# ESP-32-VEZERLO-V1.net
KiCad netlist of a schematic drawn in EAGLE
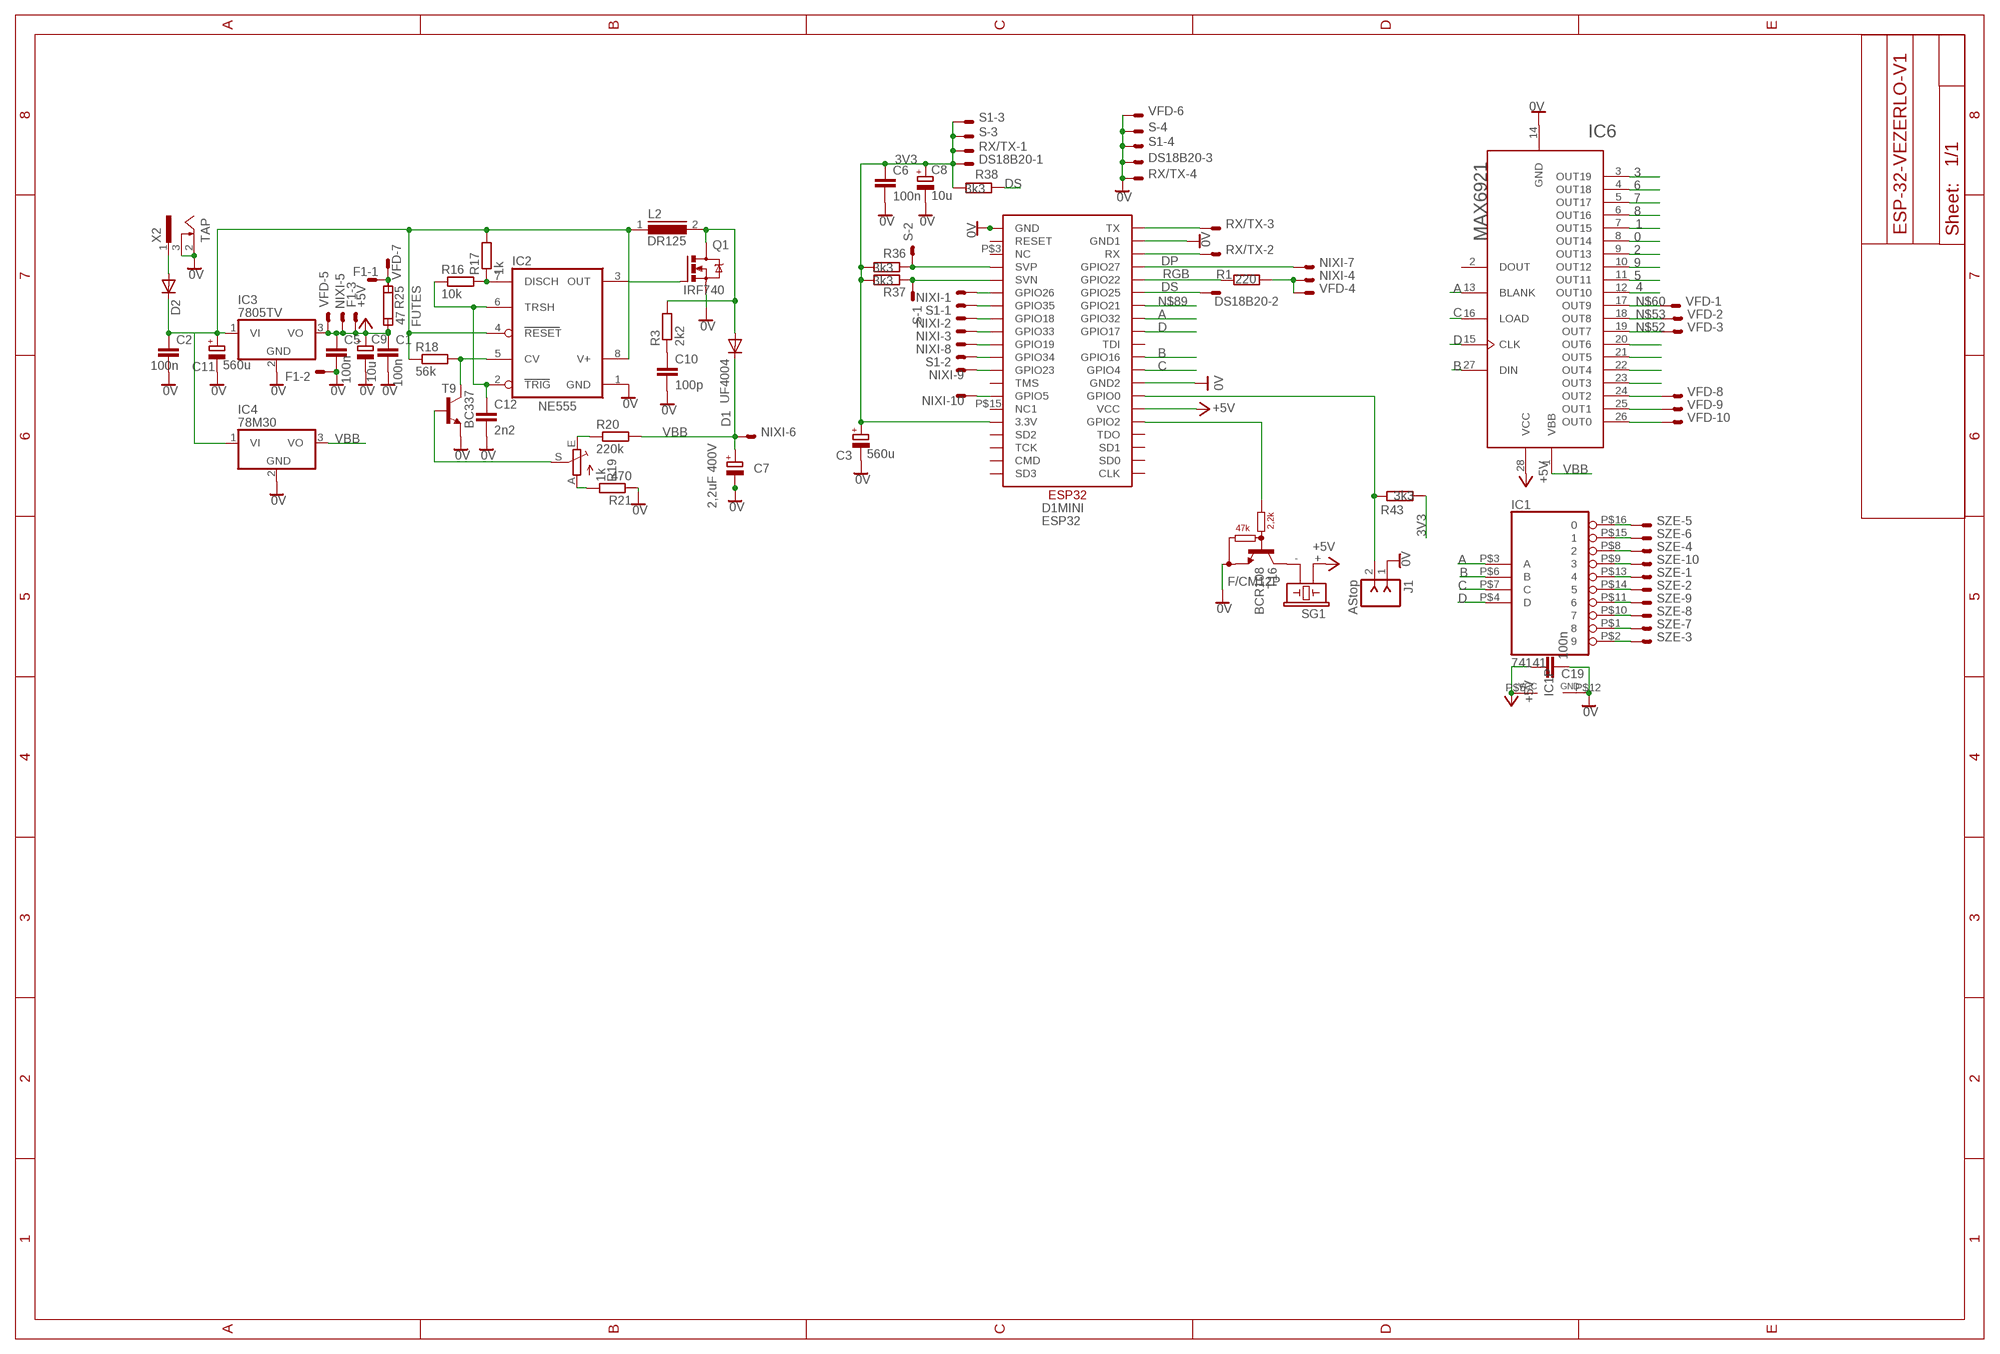
[diagram p0: schematic, sheet 1]

(export (version "E")
  (design (tool "Eeschema 10.0.6"))
  (components
    (comp (ref "C1")
      (value "100n")
      (footprint "eagle-import:0603")
      (libsource (lib "eagle-import") (part "C0603"))
    )
    (comp (ref "C2")
      (value "100n")
      (footprint "eagle-import:0603")
      (libsource (lib "eagle-import") (part "C0603"))
    )
    (comp (ref "C3")
      (value "560u")
      (footprint "eagle-import:E5-8,5")
      (libsource (lib "eagle-import") (part "CPOL-EUE5-8.5"))
    )
    (comp (ref "C5")
      (value "100n")
      (footprint "eagle-import:0603")
      (libsource (lib "eagle-import") (part "C0603"))
    )
    (comp (ref "C6")
      (value "100n")
      (footprint "eagle-import:0603")
      (libsource (lib "eagle-import") (part "C0603"))
    )
    (comp (ref "C7")
      (value "2,2uF 400V")
      (footprint "eagle-import:E2,5-7")
      (libsource (lib "eagle-import") (part "CPOL-EUE2.5-7"))
    )
    (comp (ref "C8")
      (value "10u")
      (footprint "eagle-import:E2,5-5")
      (libsource (lib "eagle-import") (part "CPOL-EUE2.5-5"))
    )
    (comp (ref "C9")
      (value "10u")
      (footprint "eagle-import:E2,5-5")
      (libsource (lib "eagle-import") (part "CPOL-EUE2.5-5"))
    )
    (comp (ref "C10")
      (value "100p")
      (footprint "eagle-import:C050-024X044")
      (libsource (lib "eagle-import") (part "C-EU050-024X044"))
    )
    (comp (ref "C11")
      (value "560u")
      (footprint "eagle-import:E5-8,5")
      (libsource (lib "eagle-import") (part "CPOL-EUE5-8.5"))
    )
    (comp (ref "C12")
      (value "2n2")
      (footprint "eagle-import:C0603")
      (libsource (lib "eagle-import") (part "C-EUC0603"))
    )
    (comp (ref "C19")
      (value "100n")
      (footprint "eagle-import:0603")
      (libsource (lib "eagle-import") (part "C0603"))
    )
    (comp (ref "D1")
      (value "UF4004")
      (footprint "eagle-import:DO35-10")
      (libsource (lib "eagle-import") (part "BA221"))
    )
    (comp (ref "D1MINI")
      (value "ESP32")
      (footprint "eagle-import:ESP32-2X20")
      (libsource (lib "eagle-import") (part "ESP32-2X20"))
    )
    (comp (ref "D2")
      (value "DIODE-SOD123")
      (footprint "eagle-import:SOD123")
      (libsource (lib "eagle-import") (part "DIODE-SOD123"))
    )
    (comp (ref "DS18B20")
      (value "PAD3")
      (footprint "eagle-import:PAD3")
      (libsource (lib "eagle-import") (part "PAD3"))
    )
    (comp (ref "F1")
      (value "PAD3")
      (footprint "eagle-import:PAD3")
      (libsource (lib "eagle-import") (part "PAD3"))
    )
    (comp (ref "FUTES")
      (value "47")
      (footprint "eagle-import:0207_10")
      (libsource (lib "eagle-import") (part "R-EU_0207/10"))
    )
    (comp (ref "IC1")
      (value "74141")
      (footprint "eagle-import:DIL16SMD")
      (libsource (lib "eagle-import") (part "74141"))
    )
    (comp (ref "IC2")
      (value "NE555")
      (footprint "eagle-import:DIL08")
      (fields (field (name "MF") "MAXIM") (field (name "MPN") "ICM7555IPA+"))
      (libsource (lib "eagle-import") (part "ICM7555"))
    )
    (comp (ref "IC3")
      (value "7805TV")
      (footprint "eagle-import:TO220V")
      (libsource (lib "eagle-import") (part "78TV05"))
    )
    (comp (ref "IC4")
      (value "78M30")
      (footprint "eagle-import:TO220V")
      (libsource (lib "eagle-import") (part "78TV05"))
    )
    (comp (ref "IC6")
      (value "MAX6921")
      (footprint "eagle-import:SO-28W")
      (libsource (lib "eagle-import") (part "MAX6921SOIC28W"))
    )
    (comp (ref "J1")
      (value "AStop")
      (footprint "eagle-import:SIP-100-02-32")
      (libsource (lib "eagle-import") (part "F-1X02-SIP-100-32"))
    )
    (comp (ref "L2")
      (value "DR125")
      (footprint "eagle-import:DR125")
      (libsource (lib "eagle-import") (part "DR125"))
    )
    (comp (ref "NIXI")
      (value "PAD10")
      (footprint "eagle-import:PAD10")
      (libsource (lib "eagle-import") (part "PAD10"))
    )
    (comp (ref "Q1")
      (value "IRF740")
      (footprint "eagle-import:TO220BV")
      (libsource (lib "eagle-import") (part "IRF740"))
    )
    (comp (ref "R1")
      (value "220")
      (footprint "eagle-import:0603")
      (libsource (lib "eagle-import") (part "R0603"))
    )
    (comp (ref "R3")
      (value "2k2")
      (footprint "eagle-import:0204_7")
      (libsource (lib "eagle-import") (part "R-EU_0204/7"))
    )
    (comp (ref "R16")
      (value "10k")
      (footprint "eagle-import:R0603")
      (libsource (lib "eagle-import") (part "R-EU_R0603"))
    )
    (comp (ref "R17")
      (value "1k")
      (footprint "eagle-import:R0603")
      (libsource (lib "eagle-import") (part "R-EU_R0603"))
    )
    (comp (ref "R18")
      (value "56k")
      (footprint "eagle-import:R0603")
      (libsource (lib "eagle-import") (part "R-EU_R0603"))
    )
    (comp (ref "R19")
      (value "1k")
      (footprint "eagle-import:CA6H")
      (libsource (lib "eagle-import") (part "TRIM_EU-CA6H"))
    )
    (comp (ref "R20")
      (value "220k")
      (footprint "eagle-import:0204_7")
      (libsource (lib "eagle-import") (part "R-EU_0204/7"))
    )
    (comp (ref "R21")
      (value "470")
      (footprint "eagle-import:0204_7")
      (libsource (lib "eagle-import") (part "R-EU_0204/7"))
    )
    (comp (ref "R25")
      (value "RCA0001")
      (footprint "eagle-import:CA0001")
      (libsource (lib "eagle-import") (part "RCA0001"))
    )
    (comp (ref "R36")
      (value "3k3")
      (footprint "eagle-import:0603")
      (libsource (lib "eagle-import") (part "R0603"))
    )
    (comp (ref "R37")
      (value "3k3")
      (footprint "eagle-import:0603")
      (libsource (lib "eagle-import") (part "R0603"))
    )
    (comp (ref "R38")
      (value "3k3")
      (footprint "eagle-import:0603")
      (libsource (lib "eagle-import") (part "R0603"))
    )
    (comp (ref "R43")
      (value "3k3")
      (footprint "eagle-import:0603")
      (libsource (lib "eagle-import") (part "R0603"))
    )
    (comp (ref "RX/TX")
      (value "PAD4")
      (footprint "eagle-import:PAD4")
      (libsource (lib "eagle-import") (part "PAD4"))
    )
    (comp (ref "S")
      (value "PAD4")
      (footprint "eagle-import:PAD4")
      (libsource (lib "eagle-import") (part "PAD4"))
    )
    (comp (ref "S1")
      (value "PAD4")
      (footprint "eagle-import:PAD4")
      (libsource (lib "eagle-import") (part "PAD4"))
    )
    (comp (ref "SG1")
      (value "F/CM12P")
      (footprint "eagle-import:F_CM12P")
      (libsource (lib "eagle-import") (part "F/CM12P"))
    )
    (comp (ref "SZE")
      (value "PAD10")
      (footprint "eagle-import:PAD10")
      (libsource (lib "eagle-import") (part "PAD10"))
    )
    (comp (ref "T9")
      (value "BC337")
      (footprint "eagle-import:SOT23-BEC")
      (libsource (lib "eagle-import") (part "-NPN-SOT23-BECBC847"))
    )
    (comp (ref "T16")
      (value "BCR108")
      (footprint "eagle-import:SOT23-BEC")
      (libsource (lib "eagle-import") (part "BCR108"))
    )
    (comp (ref "VFD")
      (value "PAD10")
      (footprint "eagle-import:PAD10")
      (libsource (lib "eagle-import") (part "PAD10"))
    )
    (comp (ref "X2")
      (value "TAP")
      (footprint "eagle-import:TAP")
      (libsource (lib "eagle-import") (part "TAP"))
    )
  )
  (nets
    (net (code "1") (name "+5V") (class "Default")
      (node (ref "C1") (pin "1") (pinfunction "1_1") (pintype "passive"))
      (node (ref "C19") (pin "1") (pinfunction "1_1") (pintype "passive"))
      (node (ref "C5") (pin "1") (pinfunction "1_1") (pintype "passive"))
      (node (ref "C9") (pin "+") (pinfunction "+_+") (pintype "passive"))
      (node (ref "D1MINI") (pin "P$35") (pinfunction "VCC_P$35") (pintype "bidirectional"))
      (node (ref "F1") (pin "P$3") (pinfunction "S_P$3") (pintype "passive"))
      (node (ref "FUTES") (pin "1") (pinfunction "1_1") (pintype "passive"))
      (node (ref "IC1") (pin "P$5") (pinfunction "VCC_P$5") (pintype "power_in"))
      (node (ref "IC3") (pin "3") (pinfunction "VO_3") (pintype "passive"))
      (node (ref "IC6") (pin "28") (pinfunction "VCC_28") (pintype "power_in"))
      (node (ref "NIXI") (pin "P$5") (pinfunction "S_P$5") (pintype "passive"))
      (node (ref "R25") (pin "1") (pinfunction "1_1") (pintype "passive"))
      (node (ref "SG1") (pin "+") (pinfunction "1_+") (pintype "passive"))
      (node (ref "VFD") (pin "P$5") (pinfunction "S_P$5") (pintype "passive"))
    )
    (net (code "2") (name "/0") (class "Default")
      (node (ref "IC1") (pin "P$16") (pinfunction "0_P$16") (pintype "open_collector"))
      (node (ref "IC6") (pin "8") (pinfunction "OUT14_8") (pintype "output"))
      (node (ref "SZE") (pin "P$5") (pinfunction "S_P$5") (pintype "passive"))
    )
    (net (code "3") (name "/1") (class "Default")
      (node (ref "IC1") (pin "P$15") (pinfunction "1_P$15") (pintype "open_collector"))
      (node (ref "IC6") (pin "7") (pinfunction "OUT15_7") (pintype "output"))
      (node (ref "SZE") (pin "P$6") (pinfunction "S_P$6") (pintype "passive"))
    )
    (net (code "4") (name "/2") (class "Default")
      (node (ref "IC1") (pin "P$8") (pinfunction "2_P$8") (pintype "open_collector"))
      (node (ref "IC6") (pin "9") (pinfunction "OUT13_9") (pintype "output"))
      (node (ref "SZE") (pin "P$4") (pinfunction "S_P$4") (pintype "passive"))
    )
    (net (code "5") (name "/3") (class "Default")
      (node (ref "IC1") (pin "P$9") (pinfunction "3_P$9") (pintype "open_collector"))
      (node (ref "IC6") (pin "3") (pinfunction "OUT19_3") (pintype "output"))
      (node (ref "SZE") (pin "P$10") (pinfunction "S_P$10") (pintype "passive"))
    )
    (net (code "6") (name "/3V3") (class "Default")
      (node (ref "C3") (pin "+") (pinfunction "+_+") (pintype "passive"))
      (node (ref "C6") (pin "1") (pinfunction "1_1") (pintype "passive"))
      (node (ref "C8") (pin "+") (pinfunction "+_+") (pintype "passive"))
      (node (ref "D1MINI") (pin "P$16") (pinfunction "3.3V_P$16") (pintype "bidirectional"))
      (node (ref "DS18B20") (pin "P$1") (pinfunction "S_P$1") (pintype "passive"))
      (node (ref "R36") (pin "2") (pinfunction "2_2") (pintype "passive"))
      (node (ref "R37") (pin "2") (pinfunction "2_2") (pintype "passive"))
      (node (ref "R38") (pin "2") (pinfunction "2_2") (pintype "passive"))
      (node (ref "R43") (pin "2") (pinfunction "2_2") (pintype "passive"))
      (node (ref "RX/TX") (pin "P$1") (pinfunction "S_P$1") (pintype "passive"))
      (node (ref "S") (pin "P$3") (pinfunction "S_P$3") (pintype "passive"))
      (node (ref "S1") (pin "P$3") (pinfunction "S_P$3") (pintype "passive"))
    )
    (net (code "7") (name "/4") (class "Default")
      (node (ref "IC1") (pin "P$13") (pinfunction "4_P$13") (pintype "open_collector"))
      (node (ref "IC6") (pin "12") (pinfunction "OUT10_12") (pintype "output"))
      (node (ref "SZE") (pin "P$1") (pinfunction "S_P$1") (pintype "passive"))
    )
    (net (code "8") (name "/5") (class "Default")
      (node (ref "IC1") (pin "P$14") (pinfunction "5_P$14") (pintype "open_collector"))
      (node (ref "IC6") (pin "11") (pinfunction "OUT11_11") (pintype "output"))
      (node (ref "SZE") (pin "P$2") (pinfunction "S_P$2") (pintype "passive"))
    )
    (net (code "9") (name "/6") (class "Default")
      (node (ref "IC1") (pin "P$11") (pinfunction "6_P$11") (pintype "open_collector"))
      (node (ref "IC6") (pin "4") (pinfunction "OUT18_4") (pintype "output"))
      (node (ref "SZE") (pin "P$9") (pinfunction "S_P$9") (pintype "passive"))
    )
    (net (code "10") (name "/7") (class "Default")
      (node (ref "IC1") (pin "P$10") (pinfunction "7_P$10") (pintype "open_collector"))
      (node (ref "IC6") (pin "5") (pinfunction "OUT17_5") (pintype "output"))
      (node (ref "SZE") (pin "P$8") (pinfunction "S_P$8") (pintype "passive"))
    )
    (net (code "11") (name "/8") (class "Default")
      (node (ref "IC1") (pin "P$1") (pinfunction "8_P$1") (pintype "open_collector"))
      (node (ref "IC6") (pin "6") (pinfunction "OUT16_6") (pintype "output"))
      (node (ref "SZE") (pin "P$7") (pinfunction "S_P$7") (pintype "passive"))
    )
    (net (code "12") (name "/9") (class "Default")
      (node (ref "IC1") (pin "P$2") (pinfunction "9_P$2") (pintype "open_collector"))
      (node (ref "IC6") (pin "10") (pinfunction "OUT12_10") (pintype "output"))
      (node (ref "SZE") (pin "P$3") (pinfunction "S_P$3") (pintype "passive"))
    )
    (net (code "13") (name "/A") (class "Default")
      (node (ref "D1MINI") (pin "P$28") (pinfunction "GPIO32_P$28") (pintype "bidirectional"))
      (node (ref "IC1") (pin "P$3") (pinfunction "A_P$3") (pintype "input"))
      (node (ref "IC6") (pin "13") (pinfunction "BLANK_13") (pintype "input"))
    )
    (net (code "14") (name "/B") (class "Default")
      (node (ref "D1MINI") (pin "P$31") (pinfunction "GPIO16_P$31") (pintype "bidirectional"))
      (node (ref "IC1") (pin "P$6") (pinfunction "B_P$6") (pintype "input"))
      (node (ref "IC6") (pin "27") (pinfunction "DIN_27") (pintype "input"))
    )
    (net (code "15") (name "/C") (class "Default")
      (node (ref "D1MINI") (pin "P$32") (pinfunction "GPIO4_P$32") (pintype "bidirectional"))
      (node (ref "IC1") (pin "P$7") (pinfunction "C_P$7") (pintype "input"))
      (node (ref "IC6") (pin "16") (pinfunction "LOAD_16") (pintype "input"))
    )
    (net (code "16") (name "/D") (class "Default")
      (node (ref "D1MINI") (pin "P$29") (pinfunction "GPIO17_P$29") (pintype "bidirectional"))
      (node (ref "IC1") (pin "P$4") (pinfunction "D_P$4") (pintype "input"))
      (node (ref "IC6") (pin "15") (pinfunction "CLK_15") (pintype "input"))
    )
    (net (code "17") (name "/DP") (class "Default")
      (node (ref "D1MINI") (pin "P$24") (pinfunction "GPIO27_P$24") (pintype "bidirectional"))
      (node (ref "NIXI") (pin "P$7") (pinfunction "S_P$7") (pintype "passive"))
    )
    (net (code "18") (name "/DS") (class "Default")
      (node (ref "D1MINI") (pin "P$26") (pinfunction "GPIO25_P$26") (pintype "bidirectional"))
      (node (ref "DS18B20") (pin "P$2") (pinfunction "S_P$2") (pintype "passive"))
      (node (ref "R38") (pin "1") (pinfunction "1_1") (pintype "passive"))
    )
    (net (code "19") (name "/N$52") (class "Default")
      (node (ref "IC6") (pin "19") (pinfunction "OUT7_19") (pintype "output"))
      (node (ref "VFD") (pin "P$3") (pinfunction "S_P$3") (pintype "passive"))
    )
    (net (code "20") (name "/N$53") (class "Default")
      (node (ref "IC6") (pin "18") (pinfunction "OUT8_18") (pintype "output"))
      (node (ref "VFD") (pin "P$2") (pinfunction "S_P$2") (pintype "passive"))
    )
    (net (code "21") (name "/N$60") (class "Default")
      (node (ref "IC6") (pin "17") (pinfunction "OUT9_17") (pintype "output"))
      (node (ref "VFD") (pin "P$1") (pinfunction "S_P$1") (pintype "passive"))
    )
    (net (code "22") (name "/N$89") (class "Default")
      (node (ref "D1MINI") (pin "P$27") (pinfunction "GPIO21_P$27") (pintype "bidirectional"))
    )
    (net (code "23") (name "/RGB") (class "Default")
      (node (ref "D1MINI") (pin "P$25") (pinfunction "GPIO22_P$25") (pintype "bidirectional"))
      (node (ref "R1") (pin "2") (pinfunction "2_2") (pintype "passive"))
    )
    (net (code "24") (name "/VBB") (class "Default")
      (node (ref "C7") (pin "+") (pinfunction "+_+") (pintype "passive"))
      (node (ref "D1") (pin "C") (pinfunction "C_C") (pintype "passive"))
      (node (ref "IC4") (pin "3") (pinfunction "VO_3") (pintype "passive"))
      (node (ref "IC6") (pin "1") (pinfunction "VBB_1") (pintype "power_in"))
      (node (ref "NIXI") (pin "P$6") (pinfunction "S_P$6") (pintype "passive"))
      (node (ref "R20") (pin "2") (pinfunction "2_2") (pintype "passive"))
    )
    (net (code "25") (name "0V") (class "Default")
      (node (ref "C1") (pin "2") (pinfunction "2_2") (pintype "passive"))
      (node (ref "C10") (pin "2") (pinfunction "2_2") (pintype "passive"))
      (node (ref "C11") (pin "-") (pinfunction "-_-") (pintype "passive"))
      (node (ref "C12") (pin "2") (pinfunction "2_2") (pintype "passive"))
      (node (ref "C19") (pin "2") (pinfunction "2_2") (pintype "passive"))
      (node (ref "C2") (pin "2") (pinfunction "2_2") (pintype "passive"))
      (node (ref "C3") (pin "-") (pinfunction "-_-") (pintype "passive"))
      (node (ref "C5") (pin "2") (pinfunction "2_2") (pintype "passive"))
      (node (ref "C6") (pin "2") (pinfunction "2_2") (pintype "passive"))
      (node (ref "C7") (pin "-") (pinfunction "-_-") (pintype "passive"))
      (node (ref "C8") (pin "-") (pinfunction "-_-") (pintype "passive"))
      (node (ref "C9") (pin "-") (pinfunction "-_-") (pintype "passive"))
      (node (ref "D1MINI") (pin "P$1") (pinfunction "GND_P$1") (pintype "bidirectional"))
      (node (ref "D1MINI") (pin "P$22") (pinfunction "GND1_P$22") (pintype "bidirectional"))
      (node (ref "D1MINI") (pin "P$33") (pinfunction "GND2_P$33") (pintype "bidirectional"))
      (node (ref "DS18B20") (pin "P$3") (pinfunction "S_P$3") (pintype "passive"))
      (node (ref "F1") (pin "P$2") (pinfunction "S_P$2") (pintype "passive"))
      (node (ref "IC1") (pin "P$12") (pinfunction "GND_P$12") (pintype "power_in"))
      (node (ref "IC2") (pin "1") (pinfunction "GND_1") (pintype "power_in"))
      (node (ref "IC3") (pin "2") (pinfunction "GND_2") (pintype "passive"))
      (node (ref "IC4") (pin "2") (pinfunction "GND_2") (pintype "passive"))
      (node (ref "IC6") (pin "14") (pinfunction "GND_14") (pintype "power_in"))
      (node (ref "J1") (pin "1") (pinfunction "1_1") (pintype "passive"))
      (node (ref "Q1") (pin "S") (pinfunction "S_S") (pintype "passive"))
      (node (ref "R21") (pin "1") (pinfunction "1_1") (pintype "passive"))
      (node (ref "RX/TX") (pin "P$4") (pinfunction "S_P$4") (pintype "passive"))
      (node (ref "S") (pin "P$4") (pinfunction "S_P$4") (pintype "passive"))
      (node (ref "S1") (pin "P$4") (pinfunction "S_P$4") (pintype "passive"))
      (node (ref "T16") (pin "E") (pinfunction "E_E") (pintype "passive"))
      (node (ref "T9") (pin "E") (pinfunction "E_E") (pintype "passive"))
      (node (ref "VFD") (pin "P$6") (pinfunction "S_P$6") (pintype "passive"))
      (node (ref "X2") (pin "2") (pinfunction "2_2") (pintype "passive"))
      (node (ref "X2") (pin "3") (pinfunction "3_3") (pintype "passive"))
    )
    (net (code "26") (name "Net-(C10-Pad1)") (class "Default")
      (node (ref "C10") (pin "1") (pinfunction "1_1") (pintype "passive"))
      (node (ref "R3") (pin "1") (pinfunction "1_1") (pintype "passive"))
    )
    (net (code "27") (name "Net-(D1-PadA)") (class "Default")
      (node (ref "D1") (pin "A") (pinfunction "A_A") (pintype "passive"))
      (node (ref "L2") (pin "2") (pinfunction "2_2") (pintype "passive"))
      (node (ref "Q1") (pin "D") (pinfunction "D_D") (pintype "passive"))
      (node (ref "R3") (pin "2") (pinfunction "2_2") (pintype "passive"))
    )
    (net (code "28") (name "Net-(D1MINI-GPIO0)") (class "Default")
      (node (ref "D1MINI") (pin "P$34") (pinfunction "GPIO0_P$34") (pintype "bidirectional"))
      (node (ref "J1") (pin "2") (pinfunction "2_2") (pintype "passive"))
      (node (ref "R43") (pin "1") (pinfunction "1_1") (pintype "passive"))
    )
    (net (code "29") (name "Net-(D1MINI-GPIO2)") (class "Default")
      (node (ref "D1MINI") (pin "P$36") (pinfunction "GPIO2_P$36") (pintype "bidirectional"))
      (node (ref "T16") (pin "B") (pinfunction "B_B") (pintype "passive"))
    )
    (net (code "30") (name "Net-(D1MINI-GPIO5)") (class "Default")
      (node (ref "D1MINI") (pin "P$14") (pinfunction "GPIO5_P$14") (pintype "bidirectional"))
      (node (ref "NIXI") (pin "P$10") (pinfunction "S_P$10") (pintype "passive"))
    )
    (net (code "31") (name "Net-(D1MINI-GPIO18)") (class "Default")
      (node (ref "D1MINI") (pin "P$8") (pinfunction "GPIO18_P$8") (pintype "bidirectional"))
      (node (ref "NIXI") (pin "P$2") (pinfunction "S_P$2") (pintype "passive"))
    )
    (net (code "32") (name "Net-(D1MINI-GPIO19)") (class "Default")
      (node (ref "D1MINI") (pin "P$10") (pinfunction "GPIO19_P$10") (pintype "bidirectional"))
      (node (ref "NIXI") (pin "P$8") (pinfunction "S_P$8") (pintype "passive"))
    )
    (net (code "33") (name "Net-(D1MINI-GPIO23)") (class "Default")
      (node (ref "D1MINI") (pin "P$12") (pinfunction "GPIO23_P$12") (pintype "bidirectional"))
      (node (ref "NIXI") (pin "P$9") (pinfunction "S_P$9") (pintype "passive"))
    )
    (net (code "34") (name "Net-(D1MINI-GPIO26)") (class "Default")
      (node (ref "D1MINI") (pin "P$6") (pinfunction "GPIO26_P$6") (pintype "bidirectional"))
      (node (ref "NIXI") (pin "P$1") (pinfunction "S_P$1") (pintype "passive"))
    )
    (net (code "35") (name "Net-(D1MINI-GPIO33)") (class "Default")
      (node (ref "D1MINI") (pin "P$9") (pinfunction "GPIO33_P$9") (pintype "bidirectional"))
      (node (ref "NIXI") (pin "P$3") (pinfunction "S_P$3") (pintype "passive"))
    )
    (net (code "36") (name "Net-(D1MINI-GPIO34)") (class "Default")
      (node (ref "D1MINI") (pin "P$11") (pinfunction "GPIO34_P$11") (pintype "bidirectional"))
      (node (ref "S1") (pin "P$2") (pinfunction "S_P$2") (pintype "passive"))
    )
    (net (code "37") (name "Net-(D1MINI-GPIO35)") (class "Default")
      (node (ref "D1MINI") (pin "P$7") (pinfunction "GPIO35_P$7") (pintype "bidirectional"))
      (node (ref "S1") (pin "P$1") (pinfunction "S_P$1") (pintype "passive"))
    )
    (net (code "38") (name "Net-(D1MINI-RX)") (class "Default")
      (node (ref "D1MINI") (pin "P$23") (pinfunction "RX_P$23") (pintype "bidirectional"))
      (node (ref "RX/TX") (pin "P$2") (pinfunction "S_P$2") (pintype "passive"))
    )
    (net (code "39") (name "Net-(D1MINI-SVN)") (class "Default")
      (node (ref "D1MINI") (pin "P$5") (pinfunction "SVN_P$5") (pintype "bidirectional"))
      (node (ref "R37") (pin "1") (pinfunction "1_1") (pintype "passive"))
      (node (ref "S") (pin "P$1") (pinfunction "S_P$1") (pintype "passive"))
    )
    (net (code "40") (name "Net-(D1MINI-SVP)") (class "Default")
      (node (ref "D1MINI") (pin "P$4") (pinfunction "SVP_P$4") (pintype "bidirectional"))
      (node (ref "R36") (pin "1") (pinfunction "1_1") (pintype "passive"))
      (node (ref "S") (pin "P$2") (pinfunction "S_P$2") (pintype "passive"))
    )
    (net (code "41") (name "Net-(D1MINI-TX)") (class "Default")
      (node (ref "D1MINI") (pin "P$21") (pinfunction "TX_P$21") (pintype "bidirectional"))
      (node (ref "RX/TX") (pin "P$3") (pinfunction "S_P$3") (pintype "passive"))
    )
    (net (code "42") (name "Net-(D2-PadA)") (class "Default")
      (node (ref "D2") (pin "A") (pinfunction "A_A") (pintype "passive"))
      (node (ref "X2") (pin "1") (pinfunction "1_1") (pintype "passive"))
    )
    (net (code "43") (name "Net-(F1A-S)") (class "Default")
      (node (ref "F1") (pin "P$1") (pinfunction "S_P$1") (pintype "passive"))
      (node (ref "FUTES") (pin "2") (pinfunction "2_2") (pintype "passive"))
      (node (ref "R25") (pin "2") (pinfunction "2_2") (pintype "passive"))
      (node (ref "VFD") (pin "P$7") (pinfunction "S_P$7") (pintype "passive"))
    )
    (net (code "44") (name "Net-(IC2-CV)") (class "Default")
      (node (ref "IC2") (pin "5") (pinfunction "CV_5") (pintype "passive"))
      (node (ref "R18") (pin "2") (pinfunction "2_2") (pintype "passive"))
      (node (ref "T9") (pin "C") (pinfunction "C_C") (pintype "passive"))
    )
    (net (code "45") (name "Net-(IC2-DISCH)") (class "Default")
      (node (ref "IC2") (pin "7") (pinfunction "DISCH_7") (pintype "input"))
      (node (ref "R16") (pin "2") (pinfunction "2_2") (pintype "passive"))
      (node (ref "R17") (pin "1") (pinfunction "1_1") (pintype "passive"))
    )
    (net (code "46") (name "Net-(IC2-OUT)") (class "Default")
      (node (ref "IC2") (pin "3") (pinfunction "OUT_3") (pintype "output"))
      (node (ref "Q1") (pin "G") (pinfunction "G_G") (pintype "passive"))
    )
    (net (code "47") (name "Net-(IC2-RESET)") (class "Default")
      (node (ref "C11") (pin "+") (pinfunction "+_+") (pintype "passive"))
      (node (ref "C2") (pin "1") (pinfunction "1_1") (pintype "passive"))
      (node (ref "D2") (pin "C") (pinfunction "C_C") (pintype "passive"))
      (node (ref "IC2") (pin "4") (pinfunction "RESET_4") (pintype "input"))
      (node (ref "IC2") (pin "8") (pinfunction "V+_8") (pintype "power_in"))
      (node (ref "IC3") (pin "1") (pinfunction "VI_1") (pintype "input"))
      (node (ref "IC4") (pin "1") (pinfunction "VI_1") (pintype "input"))
      (node (ref "L2") (pin "1") (pinfunction "1_1") (pintype "passive"))
      (node (ref "R17") (pin "2") (pinfunction "2_2") (pintype "passive"))
      (node (ref "R18") (pin "1") (pinfunction "1_1") (pintype "passive"))
    )
    (net (code "48") (name "Net-(IC2-TRIG)") (class "Default")
      (node (ref "C12") (pin "1") (pinfunction "1_1") (pintype "passive"))
      (node (ref "IC2") (pin "2") (pinfunction "TRIG_2") (pintype "bidirectional"))
      (node (ref "IC2") (pin "6") (pinfunction "TRSH_6") (pintype "input"))
      (node (ref "R16") (pin "1") (pinfunction "1_1") (pintype "passive"))
    )
    (net (code "49") (name "Net-(IC6-OUT0)") (class "Default")
      (node (ref "IC6") (pin "26") (pinfunction "OUT0_26") (pintype "output"))
      (node (ref "VFD") (pin "P$10") (pinfunction "S_P$10") (pintype "passive"))
    )
    (net (code "50") (name "Net-(IC6-OUT1)") (class "Default")
      (node (ref "IC6") (pin "25") (pinfunction "OUT1_25") (pintype "output"))
      (node (ref "VFD") (pin "P$9") (pinfunction "S_P$9") (pintype "passive"))
    )
    (net (code "51") (name "Net-(IC6-OUT2)") (class "Default")
      (node (ref "IC6") (pin "24") (pinfunction "OUT2_24") (pintype "output"))
      (node (ref "VFD") (pin "P$8") (pinfunction "S_P$8") (pintype "passive"))
    )
    (net (code "52") (name "Net-(NIXIE-S)") (class "Default")
      (node (ref "NIXI") (pin "P$4") (pinfunction "S_P$4") (pintype "passive"))
      (node (ref "R1") (pin "1") (pinfunction "1_1") (pintype "passive"))
      (node (ref "VFD") (pin "P$4") (pinfunction "S_P$4") (pintype "passive"))
    )
    (net (code "53") (name "Net-(R19-PadA)") (class "Default")
      (node (ref "R19") (pin "A") (pinfunction "A_A") (pintype "passive"))
      (node (ref "R21") (pin "2") (pinfunction "2_2") (pintype "passive"))
    )
    (net (code "54") (name "Net-(R19-PadE)") (class "Default")
      (node (ref "R19") (pin "E") (pinfunction "E_E") (pintype "passive"))
      (node (ref "R20") (pin "1") (pinfunction "1_1") (pintype "passive"))
    )
    (net (code "55") (name "Net-(R19-PadS)") (class "Default")
      (node (ref "R19") (pin "S") (pinfunction "S_S") (pintype "passive"))
      (node (ref "T9") (pin "B") (pinfunction "B_B") (pintype "passive"))
    )
    (net (code "56") (name "Net-(SG1-2)") (class "Default")
      (node (ref "SG1") (pin "-") (pinfunction "2_-") (pintype "passive"))
      (node (ref "T16") (pin "C") (pinfunction "C_C") (pintype "passive"))
    )
    (net (code "57") (name "unconnected-(D1MINI-CLK-PadP$40)") (class "Default")
      (node (ref "D1MINI") (pin "P$40") (pinfunction "CLK_P$40") (pintype "bidirectional"))
    )
    (net (code "58") (name "unconnected-(D1MINI-CMD-PadP$19)") (class "Default")
      (node (ref "D1MINI") (pin "P$19") (pinfunction "CMD_P$19") (pintype "bidirectional"))
    )
    (net (code "59") (name "unconnected-(D1MINI-NC-PadP$3)") (class "Default")
      (node (ref "D1MINI") (pin "P$3") (pinfunction "NC_P$3") (pintype "bidirectional"))
    )
    (net (code "60") (name "unconnected-(D1MINI-NC1-PadP$15)") (class "Default")
      (node (ref "D1MINI") (pin "P$15") (pinfunction "NC1_P$15") (pintype "bidirectional"))
    )
    (net (code "61") (name "unconnected-(D1MINI-RESET-PadP$2)") (class "Default")
      (node (ref "D1MINI") (pin "P$2") (pinfunction "RESET_P$2") (pintype "bidirectional"))
    )
    (net (code "62") (name "unconnected-(D1MINI-SD0-PadP$39)") (class "Default")
      (node (ref "D1MINI") (pin "P$39") (pinfunction "SD0_P$39") (pintype "bidirectional"))
    )
    (net (code "63") (name "unconnected-(D1MINI-SD1-PadP$38)") (class "Default")
      (node (ref "D1MINI") (pin "P$38") (pinfunction "SD1_P$38") (pintype "bidirectional"))
    )
    (net (code "64") (name "unconnected-(D1MINI-SD2-PadP$17)") (class "Default")
      (node (ref "D1MINI") (pin "P$17") (pinfunction "SD2_P$17") (pintype "bidirectional"))
    )
    (net (code "65") (name "unconnected-(D1MINI-SD3-PadP$20)") (class "Default")
      (node (ref "D1MINI") (pin "P$20") (pinfunction "SD3_P$20") (pintype "bidirectional"))
    )
    (net (code "66") (name "unconnected-(D1MINI-TCK-PadP$18)") (class "Default")
      (node (ref "D1MINI") (pin "P$18") (pinfunction "TCK_P$18") (pintype "bidirectional"))
    )
    (net (code "67") (name "unconnected-(D1MINI-TDI-PadP$30)") (class "Default")
      (node (ref "D1MINI") (pin "P$30") (pinfunction "TDI_P$30") (pintype "bidirectional"))
    )
    (net (code "68") (name "unconnected-(D1MINI-TDO-PadP$37)") (class "Default")
      (node (ref "D1MINI") (pin "P$37") (pinfunction "TDO_P$37") (pintype "bidirectional"))
    )
    (net (code "69") (name "unconnected-(D1MINI-TMS-PadP$13)") (class "Default")
      (node (ref "D1MINI") (pin "P$13") (pinfunction "TMS_P$13") (pintype "bidirectional"))
    )
    (net (code "70") (name "unconnected-(IC6-DOUT-Pad2)") (class "Default")
      (node (ref "IC6") (pin "2") (pinfunction "DOUT_2") (pintype "output"))
    )
    (net (code "71") (name "unconnected-(IC6-OUT3-Pad23)") (class "Default")
      (node (ref "IC6") (pin "23") (pinfunction "OUT3_23") (pintype "output"))
    )
    (net (code "72") (name "unconnected-(IC6-OUT4-Pad22)") (class "Default")
      (node (ref "IC6") (pin "22") (pinfunction "OUT4_22") (pintype "output"))
    )
    (net (code "73") (name "unconnected-(IC6-OUT5-Pad21)") (class "Default")
      (node (ref "IC6") (pin "21") (pinfunction "OUT5_21") (pintype "output"))
    )
    (net (code "74") (name "unconnected-(IC6-OUT6-Pad20)") (class "Default")
      (node (ref "IC6") (pin "20") (pinfunction "OUT6_20") (pintype "output"))
    )
  )
)
